# v1_1.net
KiCad netlist of a schematic drawn in EAGLE
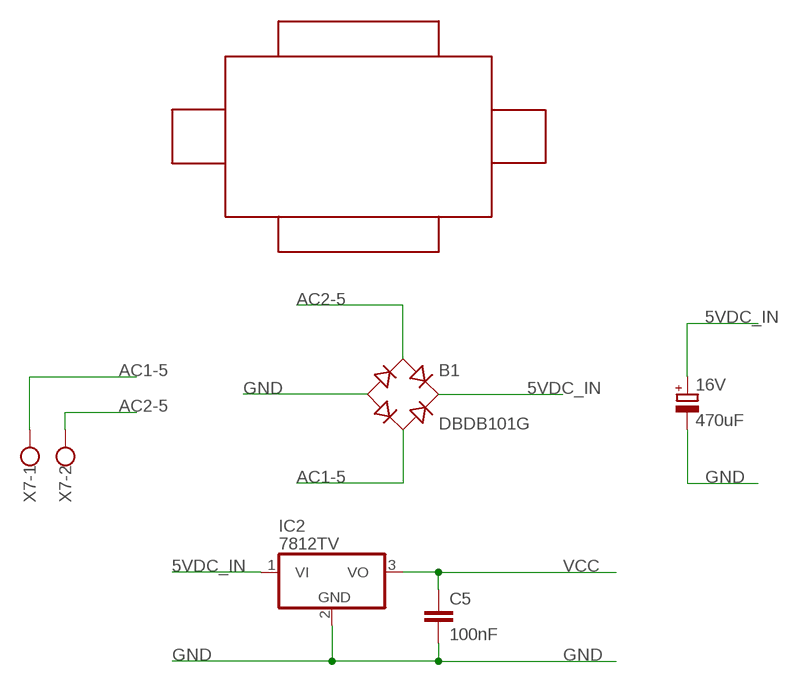
[diagram p0: schematic, sheet 1]
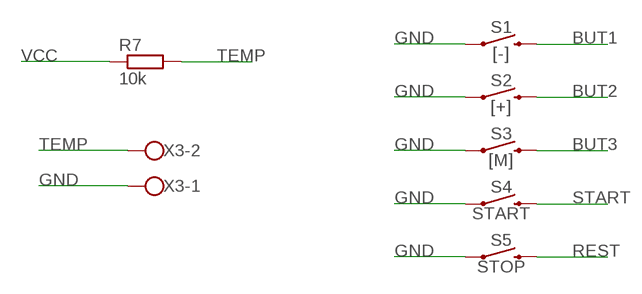
[diagram p1: schematic, sheet 2]
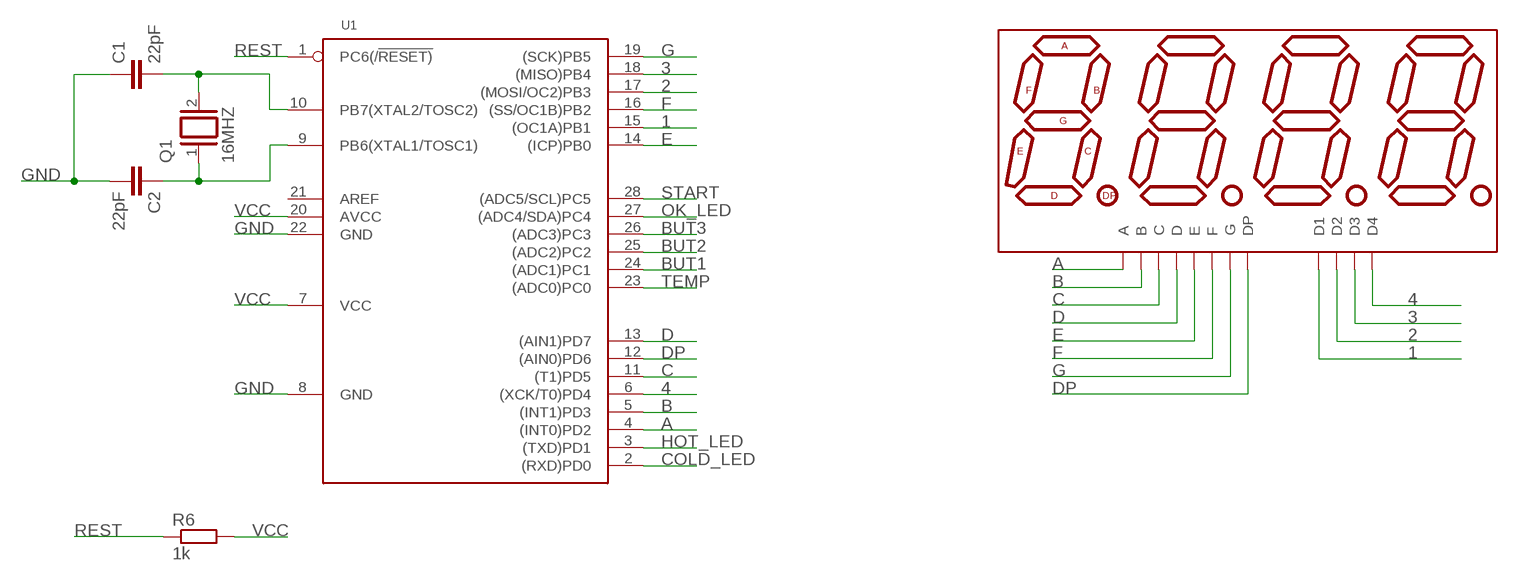
[diagram p2: schematic, sheet 3]
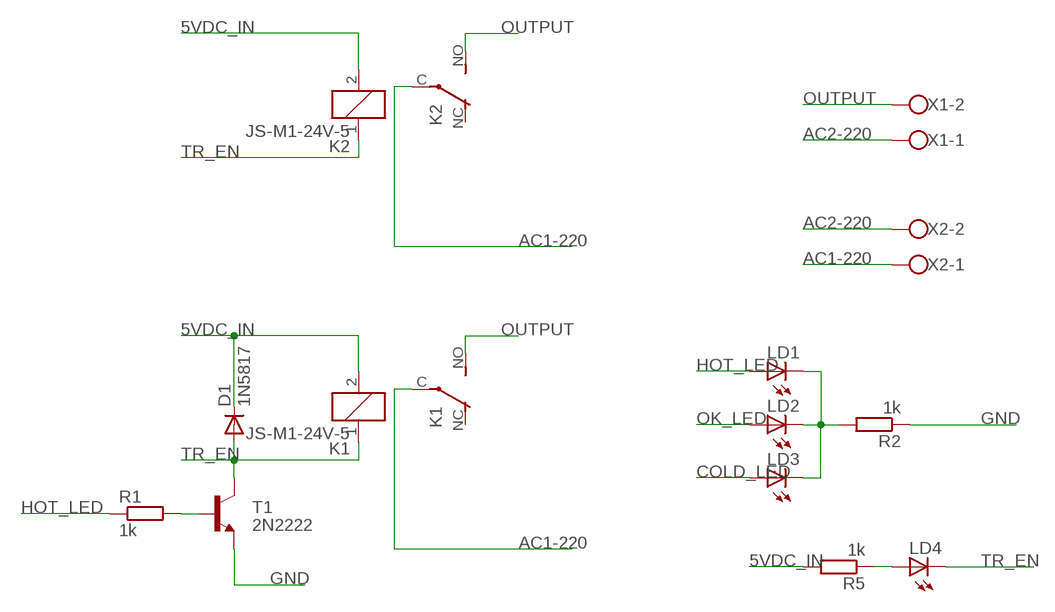
[diagram p3: schematic, sheet 4]

(export (version "E")
  (design (tool "Eeschema 10.0.6"))
  (components
    (comp (ref "16V")
      (value "470uF")
      (footprint "eagle-import:E3,5-8")
      (libsource (lib "eagle-import") (part "CPOL-EUE3.5-8"))
    )
    (comp (ref "B1")
      (value "DBDB101G")
      (footprint "eagle-import:DB")
      (libsource (lib "eagle-import") (part "DB?GDB101"))
    )
    (comp (ref "C5")
      (value "100nF")
      (footprint "eagle-import:C050-025X075")
      (libsource (lib "eagle-import") (part "C-EU050-025X075"))
    )
    (comp (ref "IC2")
      (value "7812TV")
      (footprint "eagle-import:TO220V")
      (libsource (lib "eagle-import") (part "78TV12"))
    )
    (comp (ref "U$1")
      (value "TRANS_12V")
      (footprint "eagle-import:12V")
      (libsource (lib "eagle-import") (part "TRANS_12V"))
    )
    (comp (ref "X7")
      (value "W237-102")
      (footprint "eagle-import:W237-102")
      (libsource (lib "eagle-import") (part "W237-102"))
    )
    (comp (ref "R7")
      (value "10k")
      (footprint "eagle-import:0207_10")
      (libsource (lib "eagle-import") (part "R-EU_0207/10"))
    )
    (comp (ref "S1")
      (value "[-]")
      (footprint "eagle-import:TACTILE_SWITCH_PTH_6.0MM")
      (libsource (lib "eagle-import") (part "MOMENTARY-SWITCH-SPST-PTH-6.0MM"))
    )
    (comp (ref "S2")
      (value "[+]")
      (footprint "eagle-import:TACTILE_SWITCH_PTH_6.0MM")
      (libsource (lib "eagle-import") (part "MOMENTARY-SWITCH-SPST-PTH-6.0MM"))
    )
    (comp (ref "S3")
      (value "[M]")
      (footprint "eagle-import:TACTILE_SWITCH_PTH_6.0MM")
      (libsource (lib "eagle-import") (part "MOMENTARY-SWITCH-SPST-PTH-6.0MM"))
    )
    (comp (ref "S4")
      (value "START")
      (footprint "eagle-import:TACTILE_SWITCH_PTH_6.0MM")
      (libsource (lib "eagle-import") (part "MOMENTARY-SWITCH-SPST-PTH-6.0MM"))
    )
    (comp (ref "S5")
      (value "STOP")
      (footprint "eagle-import:TACTILE_SWITCH_PTH_6.0MM")
      (libsource (lib "eagle-import") (part "MOMENTARY-SWITCH-SPST-PTH-6.0MM"))
    )
    (comp (ref "X3")
      (value "W237-102")
      (footprint "eagle-import:W237-102")
      (libsource (lib "eagle-import") (part "W237-102"))
    )
    (comp (ref "C1")
      (value "22pF")
      (footprint "eagle-import:C050-025X075")
      (libsource (lib "eagle-import") (part "C-EU050-025X075"))
    )
    (comp (ref "C2")
      (value "22pF")
      (footprint "eagle-import:C050-025X075")
      (libsource (lib "eagle-import") (part "C-EU050-025X075"))
    )
    (comp (ref "DISP2")
      (value "ATA8041AB")
      (footprint "eagle-import:7-SEGMENT-4DIGIT-20MM")
      (libsource (lib "eagle-import") (part "7-SEGMENT-4DIGIT-20MM-BLUE"))
    )
    (comp (ref "Q1")
      (value "16MHZ")
      (footprint "eagle-import:QS")
      (libsource (lib "eagle-import") (part "XTAL/S"))
    )
    (comp (ref "R6")
      (value "1k")
      (footprint "eagle-import:0207_10")
      (libsource (lib "eagle-import") (part "R-EU_0207/10"))
    )
    (comp (ref "U1")
      (value "MCU-ATMEGA328P-PU(DIP28)")
      (footprint "eagle-import:DIP28-2.54-34.7X7.62MM")
      (fields (field (name "MPN") "ATMEGA328P-PU"))
      (libsource (lib "eagle-import") (part "MCU-ATMEGA328P-PU(DIP28)"))
    )
    (comp (ref "D1")
      (value "1N5817")
      (footprint "eagle-import:DO41-10")
      (libsource (lib "eagle-import") (part "1N4004"))
    )
    (comp (ref "K1")
      (value "JS-M1-24V-5")
      (footprint "eagle-import:JS-M")
      (fields (field (name "MF") "FARNELL") (field (name "MPN") "JSM1-12V-5"))
      (libsource (lib "eagle-import") (part "JS-M1-12V-5"))
    )
    (comp (ref "K2")
      (value "JS-M1-24V-5")
      (footprint "eagle-import:JS-M")
      (fields (field (name "MF") "FARNELL") (field (name "MPN") "JSM1-12V-5"))
      (libsource (lib "eagle-import") (part "JS-M1-12V-5"))
    )
    (comp (ref "LD1")
      (value "LED5MM")
      (footprint "eagle-import:LED5MM")
      (libsource (lib "eagle-import") (part "LED5MM"))
    )
    (comp (ref "LD2")
      (value "LED5MM")
      (footprint "eagle-import:LED5MM")
      (libsource (lib "eagle-import") (part "LED5MM"))
    )
    (comp (ref "LD3")
      (value "LED5MM")
      (footprint "eagle-import:LED5MM")
      (libsource (lib "eagle-import") (part "LED5MM"))
    )
    (comp (ref "LD4")
      (value "LED5MM")
      (footprint "eagle-import:LED5MM")
      (libsource (lib "eagle-import") (part "LED5MM"))
    )
    (comp (ref "R1")
      (value "1k")
      (footprint "eagle-import:0207_10")
      (libsource (lib "eagle-import") (part "R-EU_0207/10"))
    )
    (comp (ref "R2")
      (value "1k")
      (footprint "eagle-import:0207_10")
      (libsource (lib "eagle-import") (part "R-EU_0207/10"))
    )
    (comp (ref "R5")
      (value "1k")
      (footprint "eagle-import:0207_10")
      (libsource (lib "eagle-import") (part "R-EU_0207/10"))
    )
    (comp (ref "T1")
      (value "2N2222")
      (footprint "eagle-import:TO92-EBC-OVAL")
      (libsource (lib "eagle-import") (part "2N2222"))
    )
    (comp (ref "X1")
      (value "W237-102")
      (footprint "eagle-import:W237-102")
      (libsource (lib "eagle-import") (part "W237-102"))
    )
    (comp (ref "X2")
      (value "W237-102")
      (footprint "eagle-import:W237-102")
      (libsource (lib "eagle-import") (part "W237-102"))
    )
  )
  (nets
    (net (code "1") (name "1") (class "Default")
      (node (ref "DISP2") (pin "12") (pinfunction "D1_12") (pintype "bidirectional"))
      (node (ref "U1") (pin "15") (pinfunction "(OC1A)PB1_15") (pintype "bidirectional"))
    )
    (net (code "2") (name "2") (class "Default")
      (node (ref "DISP2") (pin "9") (pinfunction "D2_9") (pintype "bidirectional"))
      (node (ref "U1") (pin "17") (pinfunction "(MOSI/OC2)PB3_17") (pintype "bidirectional"))
    )
    (net (code "3") (name "3") (class "Default")
      (node (ref "DISP2") (pin "8") (pinfunction "D3_8") (pintype "bidirectional"))
      (node (ref "U1") (pin "18") (pinfunction "(MISO)PB4_18") (pintype "bidirectional"))
    )
    (net (code "4") (name "4") (class "Default")
      (node (ref "DISP2") (pin "6") (pinfunction "D4_6") (pintype "bidirectional"))
      (node (ref "U1") (pin "6") (pinfunction "(XCK/T0)PD4_6") (pintype "bidirectional"))
    )
    (net (code "5") (name "5VDC_IN") (class "Default")
      (node (ref "16V") (pin "+") (pinfunction "+_+") (pintype "passive"))
      (node (ref "B1") (pin "+") (pinfunction "+_+") (pintype "passive"))
      (node (ref "D1") (pin "C") (pinfunction "C_C") (pintype "passive"))
      (node (ref "IC2") (pin "1") (pinfunction "VI_1") (pintype "input"))
      (node (ref "K1") (pin "2") (pinfunction "2_2") (pintype "passive"))
      (node (ref "K2") (pin "2") (pinfunction "2_2") (pintype "passive"))
      (node (ref "R5") (pin "2") (pinfunction "2_2") (pintype "passive"))
    )
    (net (code "6") (name "A") (class "Default")
      (node (ref "DISP2") (pin "11") (pinfunction "A_11") (pintype "bidirectional"))
      (node (ref "U1") (pin "4") (pinfunction "(INT0)PD2_4") (pintype "bidirectional"))
    )
    (net (code "7") (name "AC1-5") (class "Default")
      (node (ref "B1") (pin "AC2") (pinfunction "AC2_AC2") (pintype "passive"))
      (node (ref "X7") (pin "1") (pinfunction "KL_1") (pintype "passive"))
    )
    (net (code "8") (name "AC1-220") (class "Default")
      (node (ref "K1") (pin "C") (pinfunction "P_C") (pintype "passive"))
      (node (ref "K2") (pin "C") (pinfunction "P_C") (pintype "passive"))
      (node (ref "X2") (pin "1") (pinfunction "KL_1") (pintype "passive"))
    )
    (net (code "9") (name "AC2-5") (class "Default")
      (node (ref "B1") (pin "AC1") (pinfunction "AC1_AC1") (pintype "passive"))
      (node (ref "X7") (pin "2") (pinfunction "KL_2") (pintype "passive"))
    )
    (net (code "10") (name "AC2-220") (class "Default")
      (node (ref "X1") (pin "1") (pinfunction "KL_1") (pintype "passive"))
      (node (ref "X2") (pin "2") (pinfunction "KL_2") (pintype "passive"))
    )
    (net (code "11") (name "B") (class "Default")
      (node (ref "DISP2") (pin "7") (pinfunction "B_7") (pintype "bidirectional"))
      (node (ref "U1") (pin "5") (pinfunction "(INT1)PD3_5") (pintype "bidirectional"))
    )
    (net (code "12") (name "BUT1") (class "Default")
      (node (ref "S1") (pin "3") (pinfunction "2_3") (pintype "passive"))
      (node (ref "U1") (pin "24") (pinfunction "(ADC1)PC1_24") (pintype "bidirectional"))
    )
    (net (code "13") (name "BUT2") (class "Default")
      (node (ref "S2") (pin "3") (pinfunction "2_3") (pintype "passive"))
      (node (ref "U1") (pin "25") (pinfunction "(ADC2)PC2_25") (pintype "bidirectional"))
    )
    (net (code "14") (name "BUT3") (class "Default")
      (node (ref "S3") (pin "3") (pinfunction "2_3") (pintype "passive"))
      (node (ref "U1") (pin "26") (pinfunction "(ADC3)PC3_26") (pintype "bidirectional"))
    )
    (net (code "15") (name "C") (class "Default")
      (node (ref "DISP2") (pin "4") (pinfunction "C_4") (pintype "bidirectional"))
      (node (ref "U1") (pin "11") (pinfunction "(T1)PD5_11") (pintype "bidirectional"))
    )
    (net (code "16") (name "COLD_LED") (class "Default")
      (node (ref "LD3") (pin "A") (pinfunction "A_A") (pintype "passive"))
      (node (ref "U1") (pin "2") (pinfunction "(RXD)PD0_2") (pintype "bidirectional"))
    )
    (net (code "17") (name "D") (class "Default")
      (node (ref "DISP2") (pin "2") (pinfunction "D_2") (pintype "bidirectional"))
      (node (ref "U1") (pin "13") (pinfunction "(AIN1)PD7_13") (pintype "bidirectional"))
    )
    (net (code "18") (name "DP") (class "Default")
      (node (ref "DISP2") (pin "3") (pinfunction "DP_3") (pintype "bidirectional"))
      (node (ref "U1") (pin "12") (pinfunction "(AIN0)PD6_12") (pintype "bidirectional"))
    )
    (net (code "19") (name "E") (class "Default")
      (node (ref "DISP2") (pin "1") (pinfunction "E_1") (pintype "bidirectional"))
      (node (ref "U1") (pin "14") (pinfunction "(ICP)PB0_14") (pintype "bidirectional"))
    )
    (net (code "20") (name "F") (class "Default")
      (node (ref "DISP2") (pin "10") (pinfunction "F_10") (pintype "bidirectional"))
      (node (ref "U1") (pin "16") (pinfunction "(SS/OC1B)PB2_16") (pintype "bidirectional"))
    )
    (net (code "21") (name "G") (class "Default")
      (node (ref "DISP2") (pin "5") (pinfunction "G_5") (pintype "bidirectional"))
      (node (ref "U1") (pin "19") (pinfunction "(SCK)PB5_19") (pintype "bidirectional"))
    )
    (net (code "22") (name "GND") (class "Default")
      (node (ref "16V") (pin "-") (pinfunction "-_-") (pintype "passive"))
      (node (ref "B1") (pin "-") (pinfunction "-_-") (pintype "passive"))
      (node (ref "C1") (pin "1") (pinfunction "1_1") (pintype "passive"))
      (node (ref "C2") (pin "2") (pinfunction "2_2") (pintype "passive"))
      (node (ref "C5") (pin "2") (pinfunction "2_2") (pintype "passive"))
      (node (ref "IC2") (pin "2") (pinfunction "GND_2") (pintype "passive"))
      (node (ref "R2") (pin "1") (pinfunction "1_1") (pintype "passive"))
      (node (ref "S1") (pin "1") (pinfunction "1_1") (pintype "passive"))
      (node (ref "S2") (pin "1") (pinfunction "1_1") (pintype "passive"))
      (node (ref "S3") (pin "1") (pinfunction "1_1") (pintype "passive"))
      (node (ref "S4") (pin "1") (pinfunction "1_1") (pintype "passive"))
      (node (ref "S5") (pin "1") (pinfunction "1_1") (pintype "passive"))
      (node (ref "T1") (pin "E") (pinfunction "E_E") (pintype "passive"))
      (node (ref "U1") (pin "22") (pinfunction "GND_22") (pintype "bidirectional"))
      (node (ref "U1") (pin "8") (pinfunction "GND_8") (pintype "bidirectional"))
      (node (ref "X3") (pin "1") (pinfunction "KL_1") (pintype "passive"))
    )
    (net (code "23") (name "HOT_LED") (class "Default")
      (node (ref "LD1") (pin "A") (pinfunction "A_A") (pintype "passive"))
      (node (ref "R1") (pin "1") (pinfunction "1_1") (pintype "passive"))
      (node (ref "U1") (pin "3") (pinfunction "(TXD)PD1_3") (pintype "bidirectional"))
    )
    (net (code "24") (name "Net-(LD1-C)") (class "Default")
      (node (ref "LD1") (pin "K") (pinfunction "C_K") (pintype "passive"))
      (node (ref "LD2") (pin "K") (pinfunction "C_K") (pintype "passive"))
      (node (ref "LD3") (pin "K") (pinfunction "C_K") (pintype "passive"))
      (node (ref "R2") (pin "2") (pinfunction "2_2") (pintype "passive"))
    )
    (net (code "25") (name "Net-(LD4-PadA)") (class "Default")
      (node (ref "LD4") (pin "A") (pinfunction "A_A") (pintype "passive"))
      (node (ref "R5") (pin "1") (pinfunction "1_1") (pintype "passive"))
    )
    (net (code "26") (name "Net-(R1-Pad2)") (class "Default")
      (node (ref "R1") (pin "2") (pinfunction "2_2") (pintype "passive"))
      (node (ref "T1") (pin "B") (pinfunction "B_B") (pintype "passive"))
    )
    (net (code "27") (name "Net-(U1-PB6(XTAL1{slash}TOSC1))") (class "Default")
      (node (ref "C2") (pin "1") (pinfunction "1_1") (pintype "passive"))
      (node (ref "Q1") (pin "1") (pinfunction "1_1") (pintype "passive"))
      (node (ref "U1") (pin "9") (pinfunction "PB6(XTAL1/TOSC1)_9") (pintype "bidirectional"))
    )
    (net (code "28") (name "Net-(U1-PB7(XTAL2{slash}TOSC2))") (class "Default")
      (node (ref "C1") (pin "2") (pinfunction "2_2") (pintype "passive"))
      (node (ref "Q1") (pin "2") (pinfunction "2_2") (pintype "passive"))
      (node (ref "U1") (pin "10") (pinfunction "PB7(XTAL2/TOSC2)_10") (pintype "bidirectional"))
    )
    (net (code "29") (name "OK_LED") (class "Default")
      (node (ref "LD2") (pin "A") (pinfunction "A_A") (pintype "passive"))
      (node (ref "U1") (pin "27") (pinfunction "(ADC4/SDA)PC4_27") (pintype "bidirectional"))
    )
    (net (code "30") (name "OUTPUT") (class "Default")
      (node (ref "K1") (pin "NO") (pinfunction "S_NO") (pintype "passive"))
      (node (ref "K2") (pin "NO") (pinfunction "S_NO") (pintype "passive"))
      (node (ref "X1") (pin "2") (pinfunction "KL_2") (pintype "passive"))
    )
    (net (code "31") (name "REST") (class "Default")
      (node (ref "R6") (pin "1") (pinfunction "1_1") (pintype "passive"))
      (node (ref "S5") (pin "3") (pinfunction "2_3") (pintype "passive"))
      (node (ref "U1") (pin "1") (pinfunction "PC6(/~{RESET})_1") (pintype "bidirectional"))
    )
    (net (code "32") (name "START") (class "Default")
      (node (ref "S4") (pin "3") (pinfunction "2_3") (pintype "passive"))
      (node (ref "U1") (pin "28") (pinfunction "(ADC5/SCL)PC5_28") (pintype "bidirectional"))
    )
    (net (code "33") (name "TEMP") (class "Default")
      (node (ref "R7") (pin "2") (pinfunction "2_2") (pintype "passive"))
      (node (ref "U1") (pin "23") (pinfunction "(ADC0)PC0_23") (pintype "bidirectional"))
      (node (ref "X3") (pin "2") (pinfunction "KL_2") (pintype "passive"))
    )
    (net (code "34") (name "TR_EN") (class "Default")
      (node (ref "D1") (pin "A") (pinfunction "A_A") (pintype "passive"))
      (node (ref "K1") (pin "1") (pinfunction "1_1") (pintype "passive"))
      (node (ref "K2") (pin "1") (pinfunction "1_1") (pintype "passive"))
      (node (ref "LD4") (pin "K") (pinfunction "C_K") (pintype "passive"))
      (node (ref "T1") (pin "C") (pinfunction "C_C") (pintype "passive"))
    )
    (net (code "35") (name "VCC") (class "Default")
      (node (ref "C5") (pin "1") (pinfunction "1_1") (pintype "passive"))
      (node (ref "IC2") (pin "3") (pinfunction "VO_3") (pintype "passive"))
      (node (ref "R6") (pin "2") (pinfunction "2_2") (pintype "passive"))
      (node (ref "R7") (pin "1") (pinfunction "1_1") (pintype "passive"))
      (node (ref "U1") (pin "20") (pinfunction "AVCC_20") (pintype "bidirectional"))
      (node (ref "U1") (pin "7") (pinfunction "VCC_7") (pintype "bidirectional"))
    )
    (net (code "36") (name "unconnected-(K1B-O-PadNC)") (class "Default")
      (node (ref "K1") (pin "NC") (pinfunction "O_NC") (pintype "passive"))
    )
    (net (code "37") (name "unconnected-(K2B-O-PadNC)") (class "Default")
      (node (ref "K2") (pin "NC") (pinfunction "O_NC") (pintype "passive"))
    )
    (net (code "38") (name "unconnected-(U1-AREF-Pad21)") (class "Default")
      (node (ref "U1") (pin "21") (pinfunction "AREF_21") (pintype "bidirectional"))
    )
  )
)
